# Power_Supply.net
KiCad netlist of a schematic drawn in Altium Designer
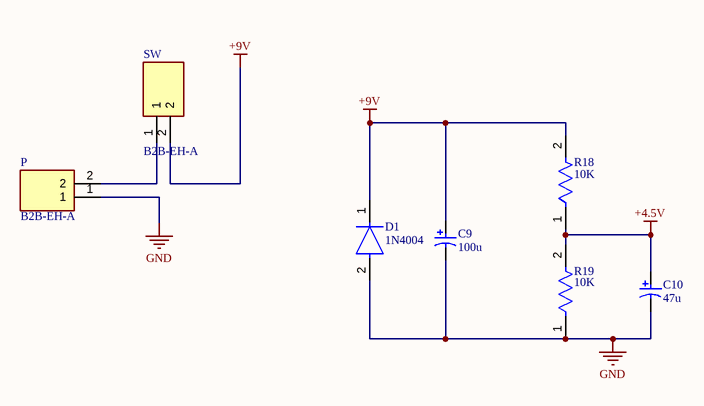
[diagram p0: Power_Supply.SchDoc]

(export (version "E")
  (design (tool "Eeschema 10.0.6"))
  (components
    (comp (ref "C9")
      (value "100u")
      (footprint "CAPPR55-200-1100X500X1200")
      (description "Aluminum Electrolytic Capacitor, 22 uF, +/- 20%, 50 V, -40 to 85 degC, 2-Pin THD, RoHS, Bulk")
      (fields (field (name "VOLTAGE") "50V") (field (name "MANUFACTURER") "Panasonic"))
      (libsource (lib "Altium Content Vault") (part "CAP-P-2"))
    )
    (comp (ref "C10")
      (value "47u")
      (footprint "CAPPR55-200-1100X500X1200")
      (description "Aluminum Electrolytic Capacitor, 22 uF, +/- 20%, 50 V, -40 to 85 degC, 2-Pin THD, RoHS, Bulk")
      (fields (field (name "VOLTAGE") "50V") (field (name "MANUFACTURER") "Panasonic"))
      (libsource (lib "Altium Content Vault") (part "CAP-P-2"))
    )
    (comp (ref "D1")
      (value "1N4004")
      (footprint "FP-1N4007-MFG")
      (description "Rectifier diode 1000 V 1 A DO-41, ,")
      (fields (field (name "MANUFACTURER PART NUMBER") "1N4007") (field (name "MANUFACTURER") "Diotec"))
      (libsource (lib "Altium Content Vault") (part "d7152d700b627762746794eb795d46e"))
    )
    (comp (ref "P")
      (value "B2B-EH-A")
      (footprint "SamacSys:SHDR2W64P0X250_1X2_750X380X600P")
      (description "Connector")
      (libsource (lib "SamacSys") (part "B2B-EH-A"))
    )
    (comp (ref "R18")
      (value "10K")
      (footprint "FP-MRS1600-MFG")
      (description "RES 20K OHM 0.4W 1% AXIAL")
      (fields (field (name "TOLERANCE") "1%"))
      (libsource (lib "Altium Content Vault") (part "1029c3af85768c4190bb7ad29bc67b5"))
    )
    (comp (ref "R19")
      (value "10K")
      (footprint "FP-MRS1600-MFG")
      (description "RES 20K OHM 0.4W 1% AXIAL")
      (fields (field (name "TOLERANCE") "1%"))
      (libsource (lib "Altium Content Vault") (part "1029c3af85768c4190bb7ad29bc67b5"))
    )
    (comp (ref "SW")
      (value "B2B-EH-A")
      (footprint "SamacSys:SHDR2W64P0X250_1X2_750X380X600P")
      (description "Connector")
      (libsource (lib "") (part "B2B-EH-A_1"))
    )
  )
  (nets
    (net (code "1") (name "+4.5V") (class "Default")
      (node (ref "C10") (pin "1") (pinfunction "1_1") (pintype "passive"))
      (node (ref "R18") (pin "1") (pinfunction "1_1") (pintype "passive"))
      (node (ref "R19") (pin "2") (pinfunction "2_2") (pintype "passive"))
    )
    (net (code "2") (name "+9V") (class "Default")
      (node (ref "C9") (pin "1") (pinfunction "1_1") (pintype "passive"))
      (node (ref "D1") (pin "1") (pinfunction "C_1") (pintype "passive"))
      (node (ref "R18") (pin "2") (pinfunction "2_2") (pintype "passive"))
      (node (ref "SW") (pin "2") (pinfunction "2_2") (pintype "passive"))
    )
    (net (code "3") (name "GND") (class "Default")
      (node (ref "C10") (pin "2") (pinfunction "2_2") (pintype "passive"))
      (node (ref "C9") (pin "2") (pinfunction "2_2") (pintype "passive"))
      (node (ref "D1") (pin "2") (pinfunction "A_2") (pintype "passive"))
      (node (ref "P") (pin "1") (pinfunction "1_1") (pintype "passive"))
      (node (ref "R19") (pin "1") (pinfunction "1_1") (pintype "passive"))
    )
    (net (code "4") (name "Net-(P-Pad2)") (class "Default")
      (node (ref "P") (pin "2") (pinfunction "2_2") (pintype "passive"))
      (node (ref "SW") (pin "1") (pinfunction "1_1") (pintype "passive"))
    )
  )
)
